# schematic.net
KiCad netlist of a schematic drawn in Altium Designer
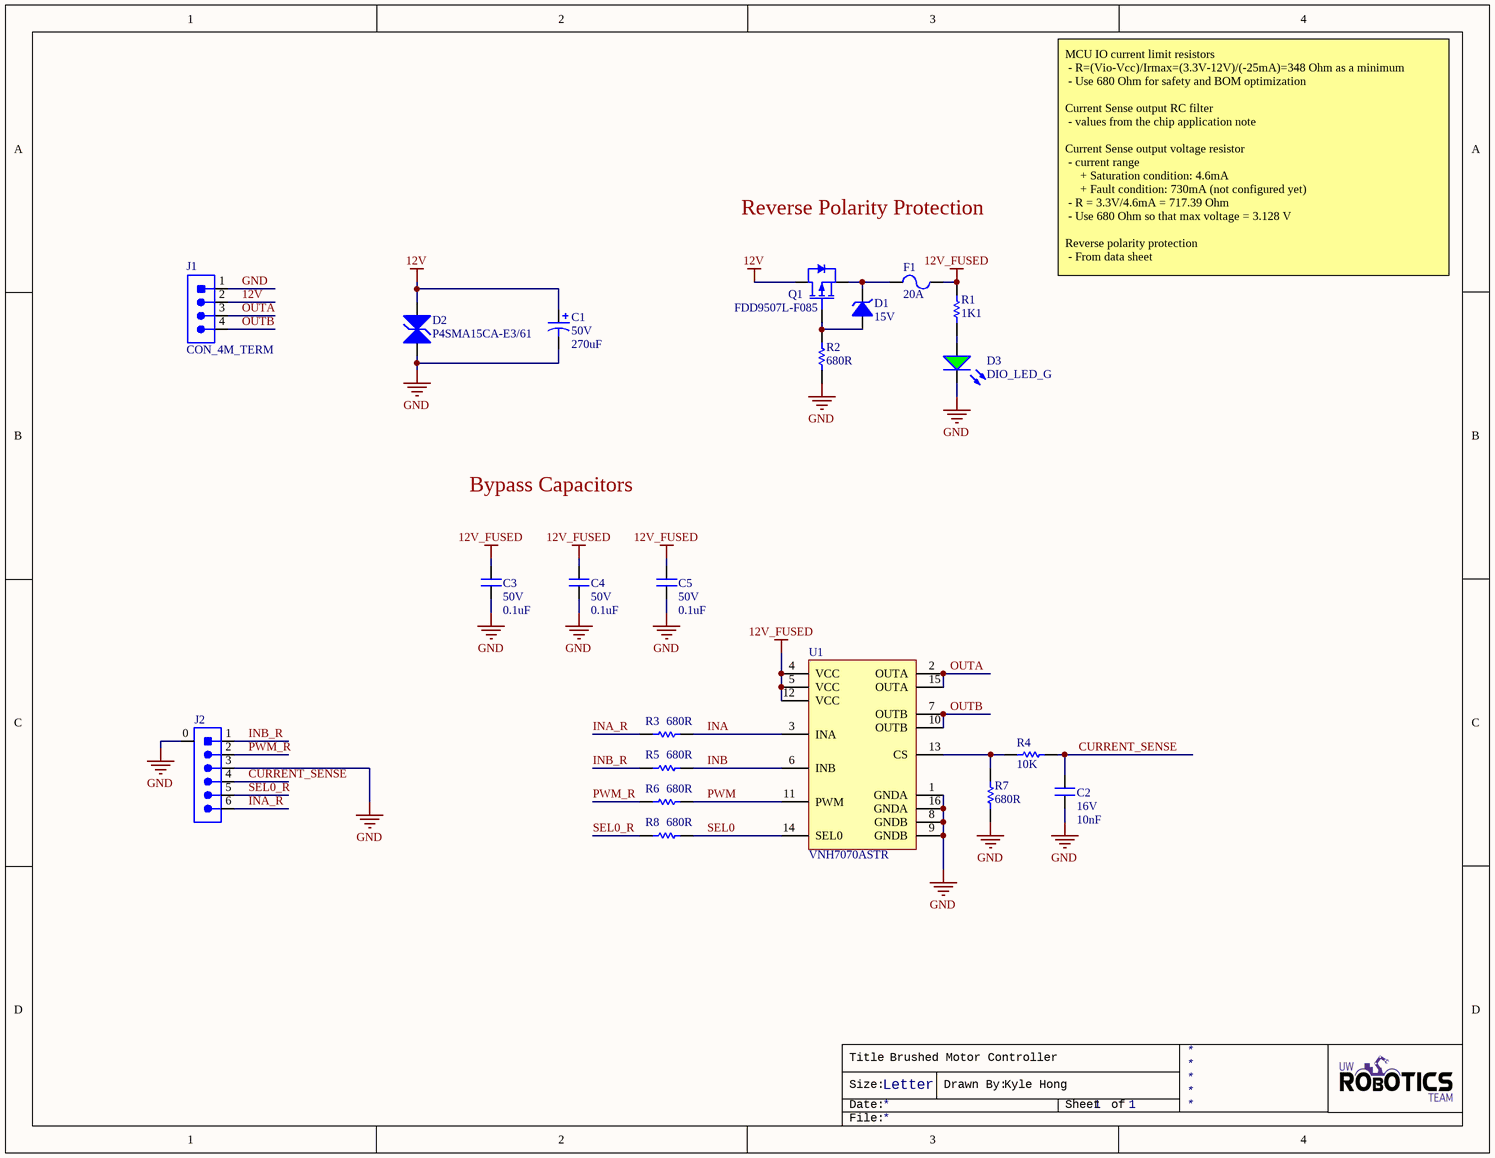
[diagram p0: schematic.SchDoc]

(export (version "E")
  (design (tool "Eeschema 10.0.6"))
  (components
    (comp (ref "C1")
      (value "CAP_270uF_50V_ALUM")
      (footprint "RADIAL_PANASONIC_G")
      (description "CAP ALUM 270UF 20% 50V RADIAL")
      (fields
        (field (name "TOLERANCE") "20%")
        (field (name "VOLTAGE RATING") "50V")
        (field (name "CAPACITANCE") "270uF")
      )
      (libsource (lib "UWRT_Schematic_Library_2020") (part "CAP_270uF_50V_ALUM"))
    )
    (comp (ref "C2")
      (value "10nF")
      (footprint "CAPC0603(1608)55_N")
      (description "CAP CER 10000PF 16V X7R 0603")
      (fields (field (name "VOLTAGE RATING") "16V") (field (name "Comment") "CAP_10nF_0603"))
      (libsource (lib "UWRT_Schematic_Library_2020") (part "CAP_10nF_0603"))
    )
    (comp (ref "C3")
      (value "0.1uF")
      (footprint "CAPC0603(1608)55_N")
      (description "CAP CER 0.1UF 50V X7R 0603")
      (fields (field (name "VOLTAGE RATING") "50V") (field (name "Comment") "CAP_0.1uF_50V_0603"))
      (libsource (lib "UWRT_Schematic_Library_2020") (part "CAP_0.1uF_50V_0603"))
    )
    (comp (ref "C4")
      (value "0.1uF")
      (footprint "CAPC0603(1608)55_N")
      (description "CAP CER 0.1UF 50V X7R 0603")
      (fields (field (name "VOLTAGE RATING") "50V") (field (name "Comment") "CAP_0.1uF_50V_0603"))
      (libsource (lib "UWRT_Schematic_Library_2020") (part "CAP_0.1uF_50V_0603"))
    )
    (comp (ref "C5")
      (value "0.1uF")
      (footprint "CAPC0603(1608)55_N")
      (description "CAP CER 0.1UF 50V X7R 0603")
      (fields (field (name "VOLTAGE RATING") "50V") (field (name "Comment") "CAP_0.1uF_50V_0603"))
      (libsource (lib "UWRT_Schematic_Library_2020") (part "CAP_0.1uF_50V_0603"))
    )
    (comp (ref "D1")
      (value "DIO_ZENER_15V")
      (footprint "SOD-323")
      (description "DIODE ZENER 15V 300mW SMD SOD-323")
      (fields (field (name "TOLERANCE") "5%") (field (name "ZENER VOLTAGE") "15V"))
      (libsource (lib "UWRT_Schematic_Library_2020") (part "DIO_ZENER_15V"))
    )
    (comp (ref "D2")
      (value "TVS_DIODE_BIDIR_12.8V")
      (footprint "TVS_DIODE_BIDIR_DO-214AC_SMA")
      (description "TVS DIODE 12.8V 21.2V SMA")
      (fields (field (name "MANUFACTURER PART NUMBER 1") "P4SMA15CA-E3/61"))
      (libsource (lib "UWRT_Schematic_Library_2020") (part "TVS_DIODE_BIDIR_12.8V"))
    )
    (comp (ref "D3")
      (value "DIO_LED_G")
      (footprint "LED_0805_LINE")
      (description "LED GREEN DIFFUSED 0805 SMD")
      (fields (field (name "MPN") "LG R971-KN-1") (field (name "MANUFACTURER") "OSRAM"))
      (libsource (lib "UWRT_Schematic_Library_2020") (part "DIO_LED_G"))
    )
    (comp (ref "F1")
      (value "FUSE_20A_1206")
      (footprint "FUSE_1206")
      (fields (field (name "CURRENT RATING") "20A"))
      (libsource (lib "UWRT_Schematic_Library_2020") (part "FUSE_20A_1206"))
    )
    (comp (ref "J1")
      (value "CON_4M_TERM")
      (footprint "UWRT_Footprint_Library_2020:1935187")
      (description "TERM BLK 4POS SIDE ENTRY 5MM PCB")
      (fields (field (name "VOLTAGE") "300V"))
      (libsource (lib "UWRT_Schematic_Library_2020") (part "CON_4M_TERM"))
    )
    (comp (ref "J2")
      (value "CON_6M_SM_RA")
      (footprint "MOLEX-5024940670")
      (description "CONN HEADER SMD RIGHT ANGLE 2MM PITCH")
      (libsource (lib "UWRT_Schematic_Library_2020") (part "CON_6M_SM_RA"))
    )
    (comp (ref "Q1")
      (value "PMOS_40V_100A")
      (footprint "D-PAK")
      (description "MOSFET P-CH 40V 100A D-PAK 4.4MOHM")
      (fields (field (name "MANUFACTURER PART NUMBER 1") "FDD9507L-F085"))
      (libsource (lib "UWRT_Schematic_Library_2020") (part "PMOS_40V_100A"))
    )
    (comp (ref "R1")
      (value "1K1")
      (footprint "RESC0603(1608)_N")
      (description "RES SMD 1.1K OHM 1% 1/10W 0603")
      (fields (field (name "TOLERANCE") "1%") (field (name "MANUFACTURER PART NUMBER") "RC0603FR-071K1L"))
      (libsource (lib "UWRT_Schematic_Library_2020") (part "RES_1K1_0603"))
    )
    (comp (ref "R2")
      (value "RES_680R_0603")
      (footprint "RESC0603(1608)_N")
      (description "RES SMD 680 OHM 5% 0.1W 0603")
      (fields (field (name "TOLERANCE") "5%") (field (name "RESISTANCE") "680R"))
      (libsource (lib "UWRT_Schematic_Library_2020") (part "RES_680R_0603"))
    )
    (comp (ref "R3")
      (value "RES_680R_0603")
      (footprint "RESC0603(1608)_N")
      (description "RES SMD 680 OHM 5% 0.1W 0603")
      (fields (field (name "TOLERANCE") "5%") (field (name "RESISTANCE") "680R"))
      (libsource (lib "UWRT_Schematic_Library_2020") (part "RES_680R_0603"))
    )
    (comp (ref "R4")
      (value "10K")
      (footprint "RESC0603(1608)_N")
      (description "RES SMD 10K OHM 5% 1/10W 0603")
      (fields (field (name "TOLERANCE") "5%") (field (name "Comment") "RES_10K_0603"))
      (libsource (lib "UWRT_Schematic_Library_2020") (part "RES_10K_0603"))
    )
    (comp (ref "R5")
      (value "RES_680R_0603")
      (footprint "RESC0603(1608)_N")
      (description "RES SMD 680 OHM 5% 0.1W 0603")
      (fields (field (name "TOLERANCE") "5%") (field (name "RESISTANCE") "680R"))
      (libsource (lib "UWRT_Schematic_Library_2020") (part "RES_680R_0603"))
    )
    (comp (ref "R6")
      (value "RES_680R_0603")
      (footprint "RESC0603(1608)_N")
      (description "RES SMD 680 OHM 5% 0.1W 0603")
      (fields (field (name "TOLERANCE") "5%") (field (name "RESISTANCE") "680R"))
      (libsource (lib "UWRT_Schematic_Library_2020") (part "RES_680R_0603"))
    )
    (comp (ref "R7")
      (value "RES_680R_0603")
      (footprint "RESC0603(1608)_N")
      (description "RES SMD 680 OHM 5% 0.1W 0603")
      (fields (field (name "TOLERANCE") "5%") (field (name "RESISTANCE") "680R"))
      (libsource (lib "UWRT_Schematic_Library_2020") (part "RES_680R_0603"))
    )
    (comp (ref "R8")
      (value "RES_680R_0603")
      (footprint "RESC0603(1608)_N")
      (description "RES SMD 680 OHM 5% 0.1W 0603")
      (fields (field (name "TOLERANCE") "5%") (field (name "RESISTANCE") "680R"))
      (libsource (lib "UWRT_Schematic_Library_2020") (part "RES_680R_0603"))
    )
    (comp (ref "U1")
      (value "IC_MOTOR_DRIVER_ST")
      (footprint "SO-16N")
      (description "IC H-BRIDGE MOTOR DRIVER 16-PINS STMicroelectronics VNH7070ASTR, SOIC")
      (fields (field (name "MANUFACTURER PART NUMBER 1") "VNH7070ASTR"))
      (libsource (lib "UWRT_Schematic_Library_2020") (part "IC_MOTOR_DRIVER_ST"))
    )
  )
  (nets
    (net (code "1") (name "/CURRENT_SENSE") (class "Default")
      (node (ref "C2") (pin "2") (pinfunction "2_2") (pintype "passive"))
      (node (ref "J2") (pin "4") (pinfunction "4_4") (pintype "passive"))
      (node (ref "R4") (pin "2") (pinfunction "2_2") (pintype "passive"))
    )
    (net (code "2") (name "/INA") (class "Default")
      (node (ref "R3") (pin "2") (pinfunction "2_2") (pintype "passive"))
      (node (ref "U1") (pin "3") (pinfunction "INA_3") (pintype "passive"))
    )
    (net (code "3") (name "/INA_R") (class "Default")
      (node (ref "J2") (pin "6") (pinfunction "6_6") (pintype "passive"))
      (node (ref "R3") (pin "1") (pinfunction "1_1") (pintype "passive"))
    )
    (net (code "4") (name "/INB") (class "Default")
      (node (ref "R5") (pin "2") (pinfunction "2_2") (pintype "passive"))
      (node (ref "U1") (pin "6") (pinfunction "INB_6") (pintype "passive"))
    )
    (net (code "5") (name "/INB_R") (class "Default")
      (node (ref "J2") (pin "1") (pinfunction "1_1") (pintype "passive"))
      (node (ref "R5") (pin "1") (pinfunction "1_1") (pintype "passive"))
    )
    (net (code "6") (name "/OUTA") (class "Default")
      (node (ref "J1") (pin "3") (pinfunction "3_3") (pintype "passive"))
      (node (ref "U1") (pin "15") (pinfunction "OUTA_15") (pintype "passive"))
      (node (ref "U1") (pin "2") (pinfunction "OUTA_2") (pintype "passive"))
    )
    (net (code "7") (name "/OUTB") (class "Default")
      (node (ref "J1") (pin "4") (pinfunction "4_4") (pintype "passive"))
      (node (ref "U1") (pin "10") (pinfunction "OUTB_10") (pintype "passive"))
      (node (ref "U1") (pin "7") (pinfunction "OUTB_7") (pintype "passive"))
    )
    (net (code "8") (name "/PWM") (class "Default")
      (node (ref "R6") (pin "2") (pinfunction "2_2") (pintype "passive"))
      (node (ref "U1") (pin "11") (pinfunction "PWM_11") (pintype "passive"))
    )
    (net (code "9") (name "/PWM_R") (class "Default")
      (node (ref "J2") (pin "2") (pinfunction "2_2") (pintype "passive"))
      (node (ref "R6") (pin "1") (pinfunction "1_1") (pintype "passive"))
    )
    (net (code "10") (name "/SEL0") (class "Default")
      (node (ref "R8") (pin "2") (pinfunction "2_2") (pintype "passive"))
      (node (ref "U1") (pin "14") (pinfunction "SEL0_14") (pintype "passive"))
    )
    (net (code "11") (name "/SEL0_R") (class "Default")
      (node (ref "J2") (pin "5") (pinfunction "5_5") (pintype "passive"))
      (node (ref "R8") (pin "1") (pinfunction "1_1") (pintype "passive"))
    )
    (net (code "12") (name "12V") (class "Default")
      (node (ref "C1") (pin "1") (pinfunction "1_1") (pintype "passive"))
      (node (ref "D2") (pin "1") (pinfunction "1_1") (pintype "passive"))
      (node (ref "J1") (pin "2") (pinfunction "2_2") (pintype "passive"))
      (node (ref "Q1") (pin "2") (pinfunction "Drain_2") (pintype "passive"))
    )
    (net (code "13") (name "12V_FUSED") (class "Default")
      (node (ref "C3") (pin "2") (pinfunction "2_2") (pintype "passive"))
      (node (ref "C4") (pin "2") (pinfunction "2_2") (pintype "passive"))
      (node (ref "C5") (pin "1") (pinfunction "1_1") (pintype "passive"))
      (node (ref "F1") (pin "2") (pinfunction "2_2") (pintype "passive"))
      (node (ref "R1") (pin "2") (pinfunction "2_2") (pintype "passive"))
      (node (ref "U1") (pin "12") (pinfunction "VCC_12") (pintype "power_in"))
      (node (ref "U1") (pin "4") (pinfunction "VCC_4") (pintype "power_in"))
      (node (ref "U1") (pin "5") (pinfunction "VCC_5") (pintype "power_in"))
    )
    (net (code "14") (name "GND") (class "Default")
      (node (ref "C1") (pin "2") (pinfunction "2_2") (pintype "passive"))
      (node (ref "C2") (pin "1") (pinfunction "1_1") (pintype "passive"))
      (node (ref "C3") (pin "1") (pinfunction "1_1") (pintype "passive"))
      (node (ref "C4") (pin "1") (pinfunction "1_1") (pintype "passive"))
      (node (ref "C5") (pin "2") (pinfunction "2_2") (pintype "passive"))
      (node (ref "D2") (pin "2") (pinfunction "2_2") (pintype "passive"))
      (node (ref "D3") (pin "2") (pinfunction "K_2") (pintype "passive"))
      (node (ref "J1") (pin "1") (pinfunction "1_1") (pintype "passive"))
      (node (ref "J2") (pin "0") (pinfunction "0_0") (pintype "passive"))
      (node (ref "J2") (pin "3") (pinfunction "3_3") (pintype "passive"))
      (node (ref "R2") (pin "1") (pinfunction "1_1") (pintype "passive"))
      (node (ref "R7") (pin "1") (pinfunction "1_1") (pintype "passive"))
      (node (ref "U1") (pin "1") (pinfunction "GNDA_1") (pintype "power_in"))
      (node (ref "U1") (pin "16") (pinfunction "GNDA_16") (pintype "power_in"))
      (node (ref "U1") (pin "8") (pinfunction "GNDB_8") (pintype "power_in"))
      (node (ref "U1") (pin "9") (pinfunction "GNDB_9") (pintype "power_in"))
    )
    (net (code "15") (name "Net-(D1-Anode)") (class "Default")
      (node (ref "D1") (pin "1") (pinfunction "Anode_1") (pintype "passive"))
      (node (ref "Q1") (pin "1") (pinfunction "Gate_1") (pintype "passive"))
      (node (ref "R2") (pin "2") (pinfunction "2_2") (pintype "passive"))
    )
    (net (code "16") (name "Net-(D1-Cathode)") (class "Default")
      (node (ref "D1") (pin "2") (pinfunction "Cathode_2") (pintype "passive"))
      (node (ref "F1") (pin "1") (pinfunction "1_1") (pintype "passive"))
      (node (ref "Q1") (pin "3") (pinfunction "Source_3") (pintype "passive"))
    )
    (net (code "17") (name "Net-(D3-A)") (class "Default")
      (node (ref "D3") (pin "1") (pinfunction "A_1") (pintype "passive"))
      (node (ref "R1") (pin "1") (pinfunction "1_1") (pintype "passive"))
    )
    (net (code "18") (name "Net-(U1-CS)") (class "Default")
      (node (ref "R4") (pin "1") (pinfunction "1_1") (pintype "passive"))
      (node (ref "R7") (pin "2") (pinfunction "2_2") (pintype "passive"))
      (node (ref "U1") (pin "13") (pinfunction "CS_13") (pintype "passive"))
    )
  )
)
